# led-cc-driver-mk-1_1.net
KiCad netlist of a schematic drawn in EAGLE
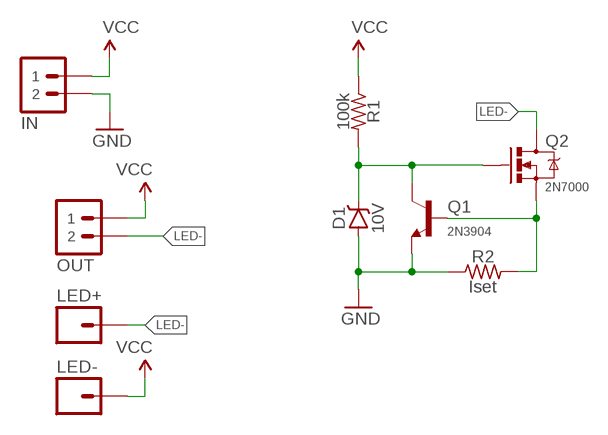
[diagram p0: schematic, sheet 1]

(export (version "E")
  (design (tool "Eeschema 10.0.6"))
  (components
    (comp (ref "D1")
      (value "10V")
      (footprint "eagle-import:DIODE-ZENNER-7.62MM")
      (libsource (lib "eagle-import") (part "DIODE-ZENER7.62MM-PTH"))
    )
    (comp (ref "IN")
      (value "M02JST-PTH-RA-SMALLPADS")
      (footprint "eagle-import:JST-2-PH-RA-PTH-SMALLPADS")
      (libsource (lib "eagle-import") (part "M02JST-PTH-RA-SMALLPADS"))
    )
    (comp (ref "LED+")
      (value "M01PTH")
      (footprint "eagle-import:1X01")
      (libsource (lib "eagle-import") (part "M01PTH"))
    )
    (comp (ref "LED-")
      (value "M01PTH")
      (footprint "eagle-import:1X01")
      (libsource (lib "eagle-import") (part "M01PTH"))
    )
    (comp (ref "OUT")
      (value "M02JST-PTH-RA-SMALLPADS")
      (footprint "eagle-import:JST-2-PH-RA-PTH-SMALLPADS")
      (libsource (lib "eagle-import") (part "M02JST-PTH-RA-SMALLPADS"))
    )
    (comp (ref "Q1")
      (value "2N3904")
      (footprint "eagle-import:TO-92-AMMO")
      (libsource (lib "eagle-import") (part "TRANSISTOR_NPNTO-92-AMMO-EBC"))
    )
    (comp (ref "Q2")
      (value "2N7000")
      (footprint "eagle-import:TO-92-AMMO")
      (libsource (lib "eagle-import") (part "MOSFET-NCHANNEL2N7000-AMMO"))
    )
    (comp (ref "R1")
      (value "100k")
      (footprint "eagle-import:RESISTOR-AXIAL-PTH-7.62MM")
      (libsource (lib "eagle-import") (part "RESISTORPTH-AXIAL-7.62MM"))
    )
    (comp (ref "R2")
      (value "Iset")
      (footprint "eagle-import:RESISTOR-AXIAL-PTH-10.16MM")
      (libsource (lib "eagle-import") (part "RESISTORPTH-AXIAL-10.16MM"))
    )
  )
  (nets
    (net (code "1") (name "GND") (class "Default")
      (node (ref "D1") (pin "A") (pinfunction "A_A") (pintype "passive"))
      (node (ref "IN") (pin "2") (pinfunction "2_2") (pintype "passive"))
      (node (ref "Q1") (pin "1") (pinfunction "E_1") (pintype "passive"))
      (node (ref "R2") (pin "P$1") (pinfunction "1_P$1") (pintype "passive"))
    )
    (net (code "2") (name "LED-") (class "Default")
      (node (ref "LED+") (pin "1") (pinfunction "1_1") (pintype "passive"))
      (node (ref "OUT") (pin "2") (pinfunction "2_2") (pintype "passive"))
      (node (ref "Q2") (pin "3") (pinfunction "D_3") (pintype "passive"))
    )
    (net (code "3") (name "Net-(D1-C)") (class "Default")
      (node (ref "D1") (pin "K") (pinfunction "C_K") (pintype "passive"))
      (node (ref "Q1") (pin "3") (pinfunction "C_3") (pintype "passive"))
      (node (ref "Q2") (pin "2") (pinfunction "G_2") (pintype "passive"))
      (node (ref "R1") (pin "P$2") (pinfunction "2_P$2") (pintype "passive"))
    )
    (net (code "4") (name "Net-(Q1-B)") (class "Default")
      (node (ref "Q1") (pin "2") (pinfunction "B_2") (pintype "passive"))
      (node (ref "Q2") (pin "1") (pinfunction "S_1") (pintype "passive"))
      (node (ref "R2") (pin "P$2") (pinfunction "2_P$2") (pintype "passive"))
    )
    (net (code "5") (name "VCC") (class "Default")
      (node (ref "IN") (pin "1") (pinfunction "1_1") (pintype "passive"))
      (node (ref "LED-") (pin "1") (pinfunction "1_1") (pintype "passive"))
      (node (ref "OUT") (pin "1") (pinfunction "1_1") (pintype "passive"))
      (node (ref "R1") (pin "P$1") (pinfunction "1_P$1") (pintype "passive"))
    )
  )
)
